# Sheet1.net
KiCad netlist of a schematic drawn in Altium Designer
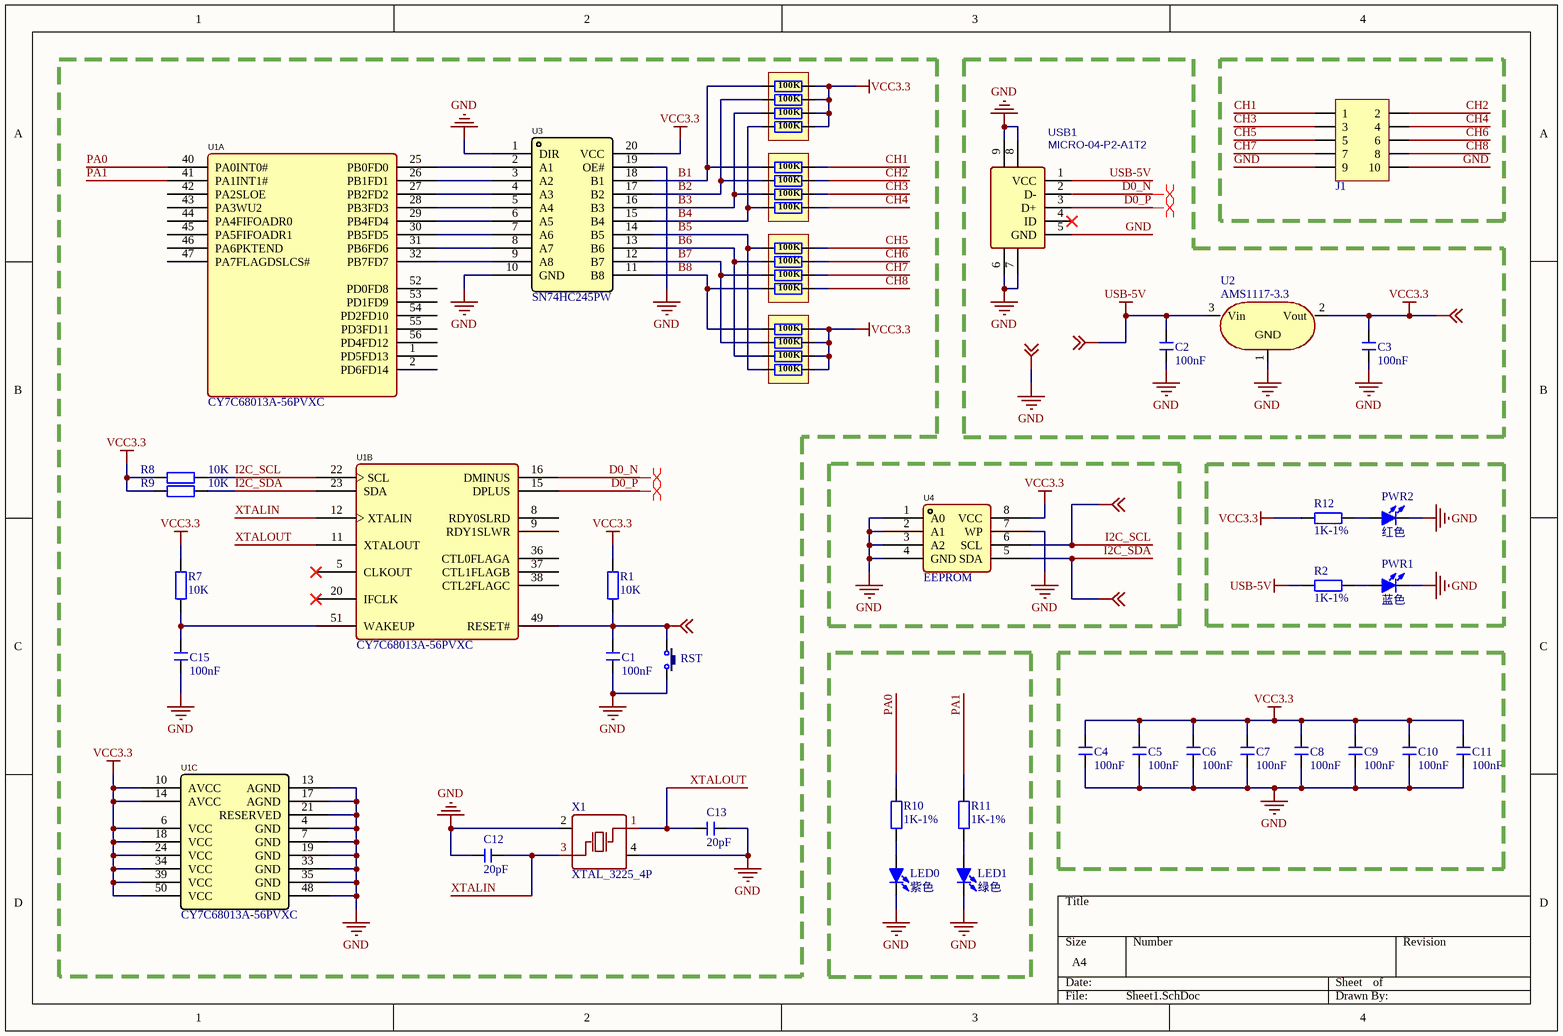
[diagram p0: Sheet1.SchDoc]

(export (version "E")
  (design (tool "Eeschema 10.0.6"))
  (components
    (comp (ref "C1")
      (value "100nF")
      (footprint "C 0603_L")
      (description "无极性贴片电容")
      (fields (field (name "版权归属") "源创客"))
      (libsource (lib "Z-LibAll") (part "C"))
    )
    (comp (ref "C2")
      (value "100nF")
      (footprint "C 0603_L")
      (description "无极性贴片电容")
      (fields (field (name "版权归属") "源创客"))
      (libsource (lib "Z-LibAll") (part "C"))
    )
    (comp (ref "C3")
      (value "100nF")
      (footprint "C 0603_L")
      (description "无极性贴片电容")
      (fields (field (name "版权归属") "源创客"))
      (libsource (lib "Z-LibAll") (part "C"))
    )
    (comp (ref "C4")
      (value "100nF")
      (footprint "C 0603_L")
      (description "无极性贴片电容")
      (fields (field (name "版权归属") "源创客"))
      (libsource (lib "Z-LibAll") (part "C"))
    )
    (comp (ref "C5")
      (value "100nF")
      (footprint "C 0603_L")
      (description "无极性贴片电容")
      (fields (field (name "版权归属") "源创客"))
      (libsource (lib "Z-LibAll") (part "C"))
    )
    (comp (ref "C6")
      (value "100nF")
      (footprint "C 0603_L")
      (description "无极性贴片电容")
      (fields (field (name "版权归属") "源创客"))
      (libsource (lib "Z-LibAll") (part "C"))
    )
    (comp (ref "C7")
      (value "100nF")
      (footprint "C 0603_L")
      (description "无极性贴片电容")
      (fields (field (name "版权归属") "源创客"))
      (libsource (lib "Z-LibAll") (part "C"))
    )
    (comp (ref "C8")
      (value "100nF")
      (footprint "C 0603_L")
      (description "无极性贴片电容")
      (fields (field (name "版权归属") "源创客"))
      (libsource (lib "Z-LibAll") (part "C"))
    )
    (comp (ref "C9")
      (value "100nF")
      (footprint "C 0603_L")
      (description "无极性贴片电容")
      (fields (field (name "版权归属") "源创客"))
      (libsource (lib "Z-LibAll") (part "C"))
    )
    (comp (ref "C10")
      (value "100nF")
      (footprint "C 0603_L")
      (description "无极性贴片电容")
      (fields (field (name "版权归属") "源创客"))
      (libsource (lib "Z-LibAll") (part "C"))
    )
    (comp (ref "C11")
      (value "100nF")
      (footprint "C 0603_L")
      (description "无极性贴片电容")
      (fields (field (name "版权归属") "源创客"))
      (libsource (lib "Z-LibAll") (part "C"))
    )
    (comp (ref "C12")
      (value "20pF")
      (footprint "C 0603_L")
      (description "无极性贴片电容")
      (fields (field (name "版权归属") "源创客"))
      (libsource (lib "Z-LibAll") (part "C"))
    )
    (comp (ref "C13")
      (value "20pF")
      (footprint "C 0603_L")
      (description "无极性贴片电容")
      (fields (field (name "版权归属") "源创客"))
      (libsource (lib "Z-LibAll") (part "C"))
    )
    (comp (ref "C15")
      (value "100nF")
      (footprint "C 0603_L")
      (description "无极性贴片电容")
      (fields (field (name "版权归属") "源创客"))
      (libsource (lib "Z-LibAll") (part "C"))
    )
    (comp (ref "J1")
      (value "Header 5X2")
      (footprint "HDR2.54-2x5P_xxx")
      (description "5*2P接插件")
      (fields (field (name "版权归属") "源创客"))
      (libsource (lib "排针-排母") (part "Header 5X2"))
    )
    (comp (ref "LED0")
      (value "紫色")
      (footprint "LED 0603B")
      (description "贴片LED")
      (fields (field (name "版权归属") "源创客"))
      (libsource (lib "LED") (part "LED-SMD"))
    )
    (comp (ref "LED1")
      (value "绿色")
      (footprint "LED 0603G")
      (description "贴片LED")
      (fields (field (name "版权归属") "源创客"))
      (libsource (lib "LED") (part "LED-SMD"))
    )
    (comp (ref "PWR1")
      (value "蓝色")
      (footprint "LED 0603B")
      (description "贴片LED")
      (fields (field (name "版权归属") "源创客"))
      (libsource (lib "LED") (part "LED-SMD"))
    )
    (comp (ref "PWR2")
      (value "红色")
      (footprint "LED 0603R")
      (description "贴片LED")
      (fields (field (name "版权归属") "源创客"))
      (libsource (lib "LED") (part "LED-SMD"))
    )
    (comp (ref "R1")
      (value "10K")
      (footprint "R 0603_L")
      (description "贴片电阻")
      (fields (field (name "版权归属") "源创客"))
      (libsource (lib "Z-LibAll") (part "R"))
    )
    (comp (ref "R2")
      (value "1K-1%")
      (footprint "R 0603_L")
      (description "贴片电阻")
      (fields (field (name "版权归属") "源创客"))
      (libsource (lib "Z-LibAll") (part "R"))
    )
    (comp (ref "R3")
      (value "100k")
      (footprint "RCA-8P4R-0402")
      (description "贴片网络排阻")
      (fields (field (name "版权归属") "源创客"))
      (libsource (lib "电阻") (part "R-8P4R"))
    )
    (comp (ref "R4")
      (value "100k")
      (footprint "RCA-8P4R-0402")
      (description "贴片网络排阻")
      (fields (field (name "版权归属") "源创客"))
      (libsource (lib "电阻") (part "R-8P4R"))
    )
    (comp (ref "R5")
      (value "100k")
      (footprint "RCA-8P4R-0402")
      (description "贴片网络排阻")
      (fields (field (name "版权归属") "源创客"))
      (libsource (lib "电阻") (part "R-8P4R"))
    )
    (comp (ref "R6")
      (value "100k")
      (footprint "RCA-8P4R-0402")
      (description "贴片网络排阻")
      (fields (field (name "版权归属") "源创客"))
      (libsource (lib "电阻") (part "R-8P4R"))
    )
    (comp (ref "R7")
      (value "10K")
      (footprint "R 0603_L")
      (description "贴片电阻")
      (fields (field (name "版权归属") "源创客"))
      (libsource (lib "Z-LibAll") (part "R"))
    )
    (comp (ref "R8")
      (value "10K")
      (footprint "R 0603_L")
      (description "贴片电阻")
      (fields (field (name "版权归属") "源创客"))
      (libsource (lib "Z-LibAll") (part "R"))
    )
    (comp (ref "R9")
      (value "10K")
      (footprint "R 0603_L")
      (description "贴片电阻")
      (fields (field (name "版权归属") "源创客"))
      (libsource (lib "Z-LibAll") (part "R"))
    )
    (comp (ref "R10")
      (value "1K-1%")
      (footprint "R 0603_L")
      (description "贴片电阻")
      (fields (field (name "版权归属") "源创客"))
      (libsource (lib "Z-LibAll") (part "R"))
    )
    (comp (ref "R11")
      (value "1K-1%")
      (footprint "R 0603_L")
      (description "贴片电阻")
      (fields (field (name "版权归属") "源创客"))
      (libsource (lib "Z-LibAll") (part "R"))
    )
    (comp (ref "R12")
      (value "1K-1%")
      (footprint "R 0603_L")
      (description "贴片电阻")
      (fields (field (name "版权归属") "源创客"))
      (libsource (lib "Z-LibAll") (part "R"))
    )
    (comp (ref "RST")
      (value "KEY_SMD")
      (footprint "KEY_SMD - duplicate1")
      (libsource (lib "Schlib") (part "KEY_SMD"))
    )
    (comp (ref "T1") (value "测试点") (footprint "测试点_2MM") (libsource (lib "Schlib") (part "测试点")))
    (comp (ref "T2") (value "测试点") (footprint "测试点_2MM") (libsource (lib "Schlib") (part "测试点")))
    (comp (ref "T3") (value "测试点") (footprint "测试点_2MM") (libsource (lib "Schlib") (part "测试点")))
    (comp (ref "T4") (value "测试点") (footprint "测试点_2MM") (libsource (lib "Schlib") (part "测试点")))
    (comp (ref "T5") (value "测试点") (footprint "测试点_3MM") (libsource (lib "Schlib") (part "测试点")))
    (comp (ref "T6") (value "测试点") (footprint "测试点_1MM") (libsource (lib "Schlib") (part "测试点")))
    (comp (ref "U1")
      (value "CY7C68013A-56PVXC")
      (footprint "CY7C68013A-56PVXC")
      (fields (field (name "MANUFACTURER") "CYPRESS(赛普拉斯)"))
      (libsource (lib "Schlib") (part "CY7C68013A-56PVXC"))
    )
    (comp (ref "U2")
      (value "AMS1117-3.3")
      (footprint "SOT223_L")
      (description "LDO")
      (libsource (lib "Z-LibAll") (part "AMS1117-3.3_C880752"))
    )
    (comp (ref "U3")
      (value "SN74HC245PW")
      (footprint "TSSOP-20")
      (description "收发器")
      (fields (field (name "MANUFACTURER") "TI(德州仪器)") (field (name "MANUFACTURER PART") "SN74HC245NSR"))
      (libsource (lib "Schlib") (part "SN74HC245NSR"))
    )
    (comp (ref "U4")
      (value "EEPROM")
      (footprint "SOP8_L")
      (description "LC_C688857")
      (fields (field (name "MANUFACTURER") "IDCHIP(英锐芯)") (field (name "MANUFACTURER PART") "AT24C02"))
      (libsource (lib "Schlib") (part "AT24C02"))
    )
    (comp (ref "USB1")
      (value "MICRO-04-P2-A1T2")
      (footprint "MICRO-04-P2-A1T2")
      (fields (field (name "BOM_SUPPLIER PART") "C2682532") (field (name "CONTRIBUTOR") "LCSC"))
      (libsource (lib "Schlib") (part "MICRO-04-P2-A1T2"))
    )
    (comp (ref "X1")
      (value "XTAL_3225_4P")
      (footprint "OSC 3225-4P")
      (description "24MHz")
      (libsource (lib "Z-LibAll") (part "XTAL"))
    )
  )
  (nets
    (net (code "1") (name "/B1") (class "Default")
      (node (ref "R3") (pin "1") (pinfunction "1_1") (pintype "passive"))
      (node (ref "R4") (pin "1") (pinfunction "1_1") (pintype "passive"))
      (node (ref "U3") (pin "18") (pinfunction "B1_18") (pintype "passive"))
    )
    (net (code "2") (name "/B2") (class "Default")
      (node (ref "R3") (pin "2") (pinfunction "2_2") (pintype "passive"))
      (node (ref "R4") (pin "2") (pinfunction "2_2") (pintype "passive"))
      (node (ref "U3") (pin "17") (pinfunction "B2_17") (pintype "passive"))
    )
    (net (code "3") (name "/B3") (class "Default")
      (node (ref "R3") (pin "3") (pinfunction "3_3") (pintype "passive"))
      (node (ref "R4") (pin "3") (pinfunction "3_3") (pintype "passive"))
      (node (ref "U3") (pin "16") (pinfunction "B3_16") (pintype "passive"))
    )
    (net (code "4") (name "/B4") (class "Default")
      (node (ref "R3") (pin "4") (pinfunction "4_4") (pintype "passive"))
      (node (ref "R4") (pin "4") (pinfunction "4_4") (pintype "passive"))
      (node (ref "U3") (pin "15") (pinfunction "B4_15") (pintype "passive"))
    )
    (net (code "5") (name "/B5") (class "Default")
      (node (ref "R5") (pin "1") (pinfunction "1_1") (pintype "passive"))
      (node (ref "R6") (pin "4") (pinfunction "4_4") (pintype "passive"))
      (node (ref "U3") (pin "14") (pinfunction "B5_14") (pintype "passive"))
    )
    (net (code "6") (name "/B6") (class "Default")
      (node (ref "R5") (pin "2") (pinfunction "2_2") (pintype "passive"))
      (node (ref "R6") (pin "3") (pinfunction "3_3") (pintype "passive"))
      (node (ref "U3") (pin "13") (pinfunction "B6_13") (pintype "passive"))
    )
    (net (code "7") (name "/B7") (class "Default")
      (node (ref "R5") (pin "3") (pinfunction "3_3") (pintype "passive"))
      (node (ref "R6") (pin "2") (pinfunction "2_2") (pintype "passive"))
      (node (ref "U3") (pin "12") (pinfunction "B7_12") (pintype "passive"))
    )
    (net (code "8") (name "/B8") (class "Default")
      (node (ref "R5") (pin "4") (pinfunction "4_4") (pintype "passive"))
      (node (ref "R6") (pin "1") (pinfunction "1_1") (pintype "passive"))
      (node (ref "U3") (pin "11") (pinfunction "B8_11") (pintype "passive"))
    )
    (net (code "9") (name "/CH1") (class "Default")
      (node (ref "J1") (pin "1") (pinfunction "1_1") (pintype "passive"))
      (node (ref "R4") (pin "8") (pinfunction "8_8") (pintype "passive"))
    )
    (net (code "10") (name "/CH2") (class "Default")
      (node (ref "J1") (pin "2") (pinfunction "2_2") (pintype "passive"))
      (node (ref "R4") (pin "7") (pinfunction "7_7") (pintype "passive"))
    )
    (net (code "11") (name "/CH3") (class "Default")
      (node (ref "J1") (pin "3") (pinfunction "3_3") (pintype "passive"))
      (node (ref "R4") (pin "6") (pinfunction "6_6") (pintype "passive"))
    )
    (net (code "12") (name "/CH4") (class "Default")
      (node (ref "J1") (pin "4") (pinfunction "4_4") (pintype "passive"))
      (node (ref "R4") (pin "5") (pinfunction "5_5") (pintype "passive"))
    )
    (net (code "13") (name "/CH5") (class "Default")
      (node (ref "J1") (pin "5") (pinfunction "5_5") (pintype "passive"))
      (node (ref "R5") (pin "8") (pinfunction "8_8") (pintype "passive"))
    )
    (net (code "14") (name "/CH6") (class "Default")
      (node (ref "J1") (pin "6") (pinfunction "6_6") (pintype "passive"))
      (node (ref "R5") (pin "7") (pinfunction "7_7") (pintype "passive"))
    )
    (net (code "15") (name "/CH7") (class "Default")
      (node (ref "J1") (pin "7") (pinfunction "7_7") (pintype "passive"))
      (node (ref "R5") (pin "6") (pinfunction "6_6") (pintype "passive"))
    )
    (net (code "16") (name "/CH8") (class "Default")
      (node (ref "J1") (pin "8") (pinfunction "8_8") (pintype "passive"))
      (node (ref "R5") (pin "5") (pinfunction "5_5") (pintype "passive"))
    )
    (net (code "17") (name "/D0_N") (class "Default")
      (node (ref "U1") (pin "16") (pinfunction "DMINUS_16") (pintype "passive"))
      (node (ref "USB1") (pin "2") (pinfunction "D-_2") (pintype "passive"))
    )
    (net (code "18") (name "/D0_P") (class "Default")
      (node (ref "U1") (pin "15") (pinfunction "DPLUS_15") (pintype "passive"))
      (node (ref "USB1") (pin "3") (pinfunction "D+_3") (pintype "passive"))
    )
    (net (code "19") (name "/I2C_SCL") (class "Default")
      (node (ref "R8") (pin "1") (pinfunction "1_1") (pintype "passive"))
      (node (ref "T3") (pin "0") (pinfunction "0_0") (pintype "passive"))
      (node (ref "U1") (pin "22") (pinfunction "SCL_22") (pintype "passive"))
      (node (ref "U4") (pin "6") (pinfunction "SCL_6") (pintype "passive"))
    )
    (net (code "20") (name "/I2C_SDA") (class "Default")
      (node (ref "R9") (pin "1") (pinfunction "1_1") (pintype "passive"))
      (node (ref "T4") (pin "0") (pinfunction "0_0") (pintype "passive"))
      (node (ref "U1") (pin "23") (pinfunction "SDA_23") (pintype "passive"))
      (node (ref "U4") (pin "5") (pinfunction "SDA_5") (pintype "passive"))
    )
    (net (code "21") (name "/PA0") (class "Default")
      (node (ref "R10") (pin "2") (pinfunction "2_2") (pintype "passive"))
      (node (ref "U1") (pin "40") (pinfunction "PA0INT0#_40") (pintype "passive"))
    )
    (net (code "22") (name "/PA1") (class "Default")
      (node (ref "R11") (pin "2") (pinfunction "2_2") (pintype "passive"))
      (node (ref "U1") (pin "41") (pinfunction "PA1INT1#_41") (pintype "passive"))
    )
    (net (code "23") (name "/XTALIN") (class "Default")
      (node (ref "C12") (pin "2") (pinfunction "2_2") (pintype "passive"))
      (node (ref "U1") (pin "12") (pinfunction "XTALIN_12") (pintype "passive"))
      (node (ref "X1") (pin "3") (pinfunction "OSC2_3") (pintype "passive"))
    )
    (net (code "24") (name "/XTALOUT") (class "Default")
      (node (ref "C13") (pin "2") (pinfunction "2_2") (pintype "passive"))
      (node (ref "U1") (pin "11") (pinfunction "XTALOUT_11") (pintype "passive"))
      (node (ref "X1") (pin "1") (pinfunction "OSC1_1") (pintype "passive"))
    )
    (net (code "25") (name "GND") (class "Default")
      (node (ref "C1") (pin "2") (pinfunction "2_2") (pintype "passive"))
      (node (ref "C10") (pin "1") (pinfunction "1_1") (pintype "passive"))
      (node (ref "C11") (pin "1") (pinfunction "1_1") (pintype "passive"))
      (node (ref "C12") (pin "1") (pinfunction "1_1") (pintype "passive"))
      (node (ref "C13") (pin "1") (pinfunction "1_1") (pintype "passive"))
      (node (ref "C15") (pin "2") (pinfunction "2_2") (pintype "passive"))
      (node (ref "C2") (pin "2") (pinfunction "2_2") (pintype "passive"))
      (node (ref "C3") (pin "2") (pinfunction "2_2") (pintype "passive"))
      (node (ref "C4") (pin "1") (pinfunction "1_1") (pintype "passive"))
      (node (ref "C5") (pin "1") (pinfunction "1_1") (pintype "passive"))
      (node (ref "C6") (pin "1") (pinfunction "1_1") (pintype "passive"))
      (node (ref "C7") (pin "1") (pinfunction "1_1") (pintype "passive"))
      (node (ref "C8") (pin "1") (pinfunction "1_1") (pintype "passive"))
      (node (ref "C9") (pin "1") (pinfunction "1_1") (pintype "passive"))
      (node (ref "J1") (pin "10") (pinfunction "10_10") (pintype "passive"))
      (node (ref "J1") (pin "9") (pinfunction "9_9") (pintype "passive"))
      (node (ref "LED0") (pin "2") (pinfunction "K_2") (pintype "passive"))
      (node (ref "LED1") (pin "2") (pinfunction "K_2") (pintype "passive"))
      (node (ref "PWR1") (pin "2") (pinfunction "K_2") (pintype "passive"))
      (node (ref "PWR2") (pin "2") (pinfunction "K_2") (pintype "passive"))
      (node (ref "RST") (pin "2") (pinfunction "2_2") (pintype "passive"))
      (node (ref "T5") (pin "0") (pinfunction "0_0") (pintype "passive"))
      (node (ref "U1") (pin "13") (pinfunction "AGND_13") (pintype "passive"))
      (node (ref "U1") (pin "17") (pinfunction "AGND_17") (pintype "passive"))
      (node (ref "U1") (pin "19") (pinfunction "GND_19") (pintype "passive"))
      (node (ref "U1") (pin "21") (pinfunction "RESERVED_21") (pintype "passive"))
      (node (ref "U1") (pin "33") (pinfunction "GND_33") (pintype "passive"))
      (node (ref "U1") (pin "35") (pinfunction "GND_35") (pintype "passive"))
      (node (ref "U1") (pin "4") (pinfunction "GND_4") (pintype "passive"))
      (node (ref "U1") (pin "48") (pinfunction "GND_48") (pintype "passive"))
      (node (ref "U1") (pin "7") (pinfunction "GND_7") (pintype "passive"))
      (node (ref "U2") (pin "1") (pinfunction "GND_1") (pintype "passive"))
      (node (ref "U3") (pin "1") (pinfunction "DIR_1") (pintype "passive"))
      (node (ref "U3") (pin "10") (pinfunction "GND_10") (pintype "passive"))
      (node (ref "U3") (pin "19") (pinfunction "OE#_19") (pintype "passive"))
      (node (ref "U4") (pin "1") (pinfunction "A0_1") (pintype "passive"))
      (node (ref "U4") (pin "2") (pinfunction "A1_2") (pintype "passive"))
      (node (ref "U4") (pin "3") (pinfunction "A2_3") (pintype "passive"))
      (node (ref "U4") (pin "4") (pinfunction "GND_4") (pintype "passive"))
      (node (ref "U4") (pin "7") (pinfunction "WP_7") (pintype "passive"))
      (node (ref "USB1") (pin "5") (pinfunction "GND_5") (pintype "passive"))
      (node (ref "USB1") (pin "6") (pinfunction "6_6") (pintype "passive"))
      (node (ref "USB1") (pin "7") (pinfunction "7_7") (pintype "passive"))
      (node (ref "USB1") (pin "8") (pinfunction "8_8") (pintype "passive"))
      (node (ref "USB1") (pin "9") (pinfunction "9_9") (pintype "passive"))
      (node (ref "X1") (pin "2") (pinfunction "GND_2") (pintype "passive"))
      (node (ref "X1") (pin "4") (pinfunction "GND_4") (pintype "passive"))
    )
    (net (code "26") (name "Net-(LED0-A)") (class "Default")
      (node (ref "LED0") (pin "1") (pinfunction "A_1") (pintype "passive"))
      (node (ref "R10") (pin "1") (pinfunction "1_1") (pintype "passive"))
    )
    (net (code "27") (name "Net-(LED1-A)") (class "Default")
      (node (ref "LED1") (pin "1") (pinfunction "A_1") (pintype "passive"))
      (node (ref "R11") (pin "1") (pinfunction "1_1") (pintype "passive"))
    )
    (net (code "28") (name "Net-(PWR1-A)") (class "Default")
      (node (ref "PWR1") (pin "1") (pinfunction "A_1") (pintype "passive"))
      (node (ref "R2") (pin "1") (pinfunction "1_1") (pintype "passive"))
    )
    (net (code "29") (name "Net-(PWR2-A)") (class "Default")
      (node (ref "PWR2") (pin "1") (pinfunction "A_1") (pintype "passive"))
      (node (ref "R12") (pin "1") (pinfunction "1_1") (pintype "passive"))
    )
    (net (code "30") (name "Net-(U1A-PB0FD0)") (class "Default")
      (node (ref "U1") (pin "25") (pinfunction "PB0FD0_25") (pintype "passive"))
      (node (ref "U3") (pin "2") (pinfunction "A1_2") (pintype "passive"))
    )
    (net (code "31") (name "Net-(U1A-PB1FD1)") (class "Default")
      (node (ref "U1") (pin "26") (pinfunction "PB1FD1_26") (pintype "passive"))
      (node (ref "U3") (pin "3") (pinfunction "A2_3") (pintype "passive"))
    )
    (net (code "32") (name "Net-(U1A-PB2FD2)") (class "Default")
      (node (ref "U1") (pin "27") (pinfunction "PB2FD2_27") (pintype "passive"))
      (node (ref "U3") (pin "4") (pinfunction "A3_4") (pintype "passive"))
    )
    (net (code "33") (name "Net-(U1A-PB3FD3)") (class "Default")
      (node (ref "U1") (pin "28") (pinfunction "PB3FD3_28") (pintype "passive"))
      (node (ref "U3") (pin "5") (pinfunction "A4_5") (pintype "passive"))
    )
    (net (code "34") (name "Net-(U1A-PB4FD4)") (class "Default")
      (node (ref "U1") (pin "29") (pinfunction "PB4FD4_29") (pintype "passive"))
      (node (ref "U3") (pin "6") (pinfunction "A5_6") (pintype "passive"))
    )
    (net (code "35") (name "Net-(U1A-PB5FD5)") (class "Default")
      (node (ref "U1") (pin "30") (pinfunction "PB5FD5_30") (pintype "passive"))
      (node (ref "U3") (pin "7") (pinfunction "A6_7") (pintype "passive"))
    )
    (net (code "36") (name "Net-(U1A-PB6FD6)") (class "Default")
      (node (ref "U1") (pin "31") (pinfunction "PB6FD6_31") (pintype "passive"))
      (node (ref "U3") (pin "8") (pinfunction "A7_8") (pintype "passive"))
    )
    (net (code "37") (name "Net-(U1A-PB7FD7)") (class "Default")
      (node (ref "U1") (pin "32") (pinfunction "PB7FD7_32") (pintype "passive"))
      (node (ref "U3") (pin "9") (pinfunction "A8_9") (pintype "passive"))
    )
    (net (code "38") (name "Net-(U1B-RESET#)") (class "Default")
      (node (ref "C1") (pin "1") (pinfunction "1_1") (pintype "passive"))
      (node (ref "R1") (pin "1") (pinfunction "1_1") (pintype "passive"))
      (node (ref "RST") (pin "1") (pinfunction "1_1") (pintype "passive"))
      (node (ref "T6") (pin "0") (pinfunction "0_0") (pintype "passive"))
      (node (ref "U1") (pin "49") (pinfunction "RESET#_49") (pintype "passive"))
    )
    (net (code "39") (name "Net-(U1B-WAKEUP)") (class "Default")
      (node (ref "C15") (pin "1") (pinfunction "1_1") (pintype "passive"))
      (node (ref "R7") (pin "1") (pinfunction "1_1") (pintype "passive"))
      (node (ref "U1") (pin "51") (pinfunction "WAKEUP_51") (pintype "passive"))
    )
    (net (code "40") (name "USB-5V") (class "Default")
      (node (ref "C2") (pin "1") (pinfunction "1_1") (pintype "passive"))
      (node (ref "R2") (pin "2") (pinfunction "2_2") (pintype "passive"))
      (node (ref "T2") (pin "0") (pinfunction "0_0") (pintype "passive"))
      (node (ref "U2") (pin "3") (pinfunction "Vin_3") (pintype "passive"))
      (node (ref "USB1") (pin "1") (pinfunction "VCC_1") (pintype "passive"))
    )
    (net (code "41") (name "VCC3.3") (class "Default")
      (node (ref "C10") (pin "2") (pinfunction "2_2") (pintype "passive"))
      (node (ref "C11") (pin "2") (pinfunction "2_2") (pintype "passive"))
      (node (ref "C3") (pin "1") (pinfunction "1_1") (pintype "passive"))
      (node (ref "C4") (pin "2") (pinfunction "2_2") (pintype "passive"))
      (node (ref "C5") (pin "2") (pinfunction "2_2") (pintype "passive"))
      (node (ref "C6") (pin "2") (pinfunction "2_2") (pintype "passive"))
      (node (ref "C7") (pin "2") (pinfunction "2_2") (pintype "passive"))
      (node (ref "C8") (pin "2") (pinfunction "2_2") (pintype "passive"))
      (node (ref "C9") (pin "2") (pinfunction "2_2") (pintype "passive"))
      (node (ref "R1") (pin "2") (pinfunction "2_2") (pintype "passive"))
      (node (ref "R12") (pin "2") (pinfunction "2_2") (pintype "passive"))
      (node (ref "R3") (pin "5") (pinfunction "5_5") (pintype "passive"))
      (node (ref "R3") (pin "6") (pinfunction "6_6") (pintype "passive"))
      (node (ref "R3") (pin "7") (pinfunction "7_7") (pintype "passive"))
      (node (ref "R3") (pin "8") (pinfunction "8_8") (pintype "passive"))
      (node (ref "R6") (pin "5") (pinfunction "5_5") (pintype "passive"))
      (node (ref "R6") (pin "6") (pinfunction "6_6") (pintype "passive"))
      (node (ref "R6") (pin "7") (pinfunction "7_7") (pintype "passive"))
      (node (ref "R6") (pin "8") (pinfunction "8_8") (pintype "passive"))
      (node (ref "R7") (pin "2") (pinfunction "2_2") (pintype "passive"))
      (node (ref "R8") (pin "2") (pinfunction "2_2") (pintype "passive"))
      (node (ref "R9") (pin "2") (pinfunction "2_2") (pintype "passive"))
      (node (ref "T1") (pin "0") (pinfunction "0_0") (pintype "passive"))
      (node (ref "U1") (pin "10") (pinfunction "AVCC_10") (pintype "passive"))
      (node (ref "U1") (pin "14") (pinfunction "AVCC_14") (pintype "passive"))
      (node (ref "U1") (pin "18") (pinfunction "VCC_18") (pintype "passive"))
      (node (ref "U1") (pin "24") (pinfunction "VCC_24") (pintype "passive"))
      (node (ref "U1") (pin "34") (pinfunction "VCC_34") (pintype "passive"))
      (node (ref "U1") (pin "39") (pinfunction "VCC_39") (pintype "passive"))
      (node (ref "U1") (pin "50") (pinfunction "VCC_50") (pintype "passive"))
      (node (ref "U1") (pin "6") (pinfunction "VCC_6") (pintype "passive"))
      (node (ref "U2") (pin "2") (pinfunction "Vout_2") (pintype "passive"))
      (node (ref "U3") (pin "20") (pinfunction "VCC_20") (pintype "passive"))
      (node (ref "U4") (pin "8") (pinfunction "VCC_8") (pintype "passive"))
    )
    (net (code "42") (name "unconnected-(U1A-PA2SLOE-Pad42)") (class "Default")
      (node (ref "U1") (pin "42") (pinfunction "PA2SLOE_42") (pintype "passive"))
    )
    (net (code "43") (name "unconnected-(U1A-PA3WU2-Pad43)") (class "Default")
      (node (ref "U1") (pin "43") (pinfunction "PA3WU2_43") (pintype "passive"))
    )
    (net (code "44") (name "unconnected-(U1A-PA4FIFOADR0-Pad44)") (class "Default")
      (node (ref "U1") (pin "44") (pinfunction "PA4FIFOADR0_44") (pintype "passive"))
    )
    (net (code "45") (name "unconnected-(U1A-PA5FIFOADR1-Pad45)") (class "Default")
      (node (ref "U1") (pin "45") (pinfunction "PA5FIFOADR1_45") (pintype "passive"))
    )
    (net (code "46") (name "unconnected-(U1A-PA6PKTEND-Pad46)") (class "Default")
      (node (ref "U1") (pin "46") (pinfunction "PA6PKTEND_46") (pintype "passive"))
    )
    (net (code "47") (name "unconnected-(U1A-PA7FLAGDSLCS#-Pad47)") (class "Default")
      (node (ref "U1") (pin "47") (pinfunction "PA7FLAGDSLCS#_47") (pintype "passive"))
    )
    (net (code "48") (name "unconnected-(U1A-PD0FD8-Pad52)") (class "Default")
      (node (ref "U1") (pin "52") (pinfunction "PD0FD8_52") (pintype "passive"))
    )
    (net (code "49") (name "unconnected-(U1A-PD1FD9-Pad53)") (class "Default")
      (node (ref "U1") (pin "53") (pinfunction "PD1FD9_53") (pintype "passive"))
    )
    (net (code "50") (name "unconnected-(U1A-PD2FD10-Pad54)") (class "Default")
      (node (ref "U1") (pin "54") (pinfunction "PD2FD10_54") (pintype "passive"))
    )
    (net (code "51") (name "unconnected-(U1A-PD3FD11-Pad55)") (class "Default")
      (node (ref "U1") (pin "55") (pinfunction "PD3FD11_55") (pintype "passive"))
    )
    (net (code "52") (name "unconnected-(U1A-PD4FD12-Pad56)") (class "Default")
      (node (ref "U1") (pin "56") (pinfunction "PD4FD12_56") (pintype "passive"))
    )
    (net (code "53") (name "unconnected-(U1A-PD5FD13-Pad1)") (class "Default")
      (node (ref "U1") (pin "1") (pinfunction "PD5FD13_1") (pintype "passive"))
    )
    (net (code "54") (name "unconnected-(U1A-PD6FD14-Pad2)") (class "Default")
      (node (ref "U1") (pin "2") (pinfunction "PD6FD14_2") (pintype "passive"))
    )
    (net (code "55") (name "unconnected-(U1A-PD7FD15-Pad3)") (class "Default")
      (node (ref "U1") (pin "3") (pinfunction "PD7FD15_3") (pintype "passive"))
    )
    (net (code "56") (name "unconnected-(U1B-CLKOUT-Pad5)") (class "Default")
      (node (ref "U1") (pin "5") (pinfunction "CLKOUT_5") (pintype "passive+no_connect"))
    )
    (net (code "57") (name "unconnected-(U1B-CTL0FLAGA-Pad36)") (class "Default")
      (node (ref "U1") (pin "36") (pinfunction "CTL0FLAGA_36") (pintype "passive"))
    )
    (net (code "58") (name "unconnected-(U1B-CTL1FLAGB-Pad37)") (class "Default")
      (node (ref "U1") (pin "37") (pinfunction "CTL1FLAGB_37") (pintype "passive"))
    )
    (net (code "59") (name "unconnected-(U1B-CTL2FLAGC-Pad38)") (class "Default")
      (node (ref "U1") (pin "38") (pinfunction "CTL2FLAGC_38") (pintype "passive"))
    )
    (net (code "60") (name "unconnected-(U1B-IFCLK-Pad20)") (class "Default")
      (node (ref "U1") (pin "20") (pinfunction "IFCLK_20") (pintype "passive+no_connect"))
    )
    (net (code "61") (name "unconnected-(U1B-RDY0SLRD-Pad8)") (class "Default")
      (node (ref "U1") (pin "8") (pinfunction "RDY0SLRD_8") (pintype "passive"))
    )
    (net (code "62") (name "unconnected-(U1B-RDY1SLWR-Pad9)") (class "Default")
      (node (ref "U1") (pin "9") (pinfunction "RDY1SLWR_9") (pintype "passive"))
    )
    (net (code "63") (name "unconnected-(USB1-ID-Pad4)") (class "Default")
      (node (ref "USB1") (pin "4") (pinfunction "ID_4") (pintype "passive+no_connect"))
    )
  )
)
